# CHM_A_32_ver1_1.net
KiCad netlist of a schematic drawn in EasyEDA Pro
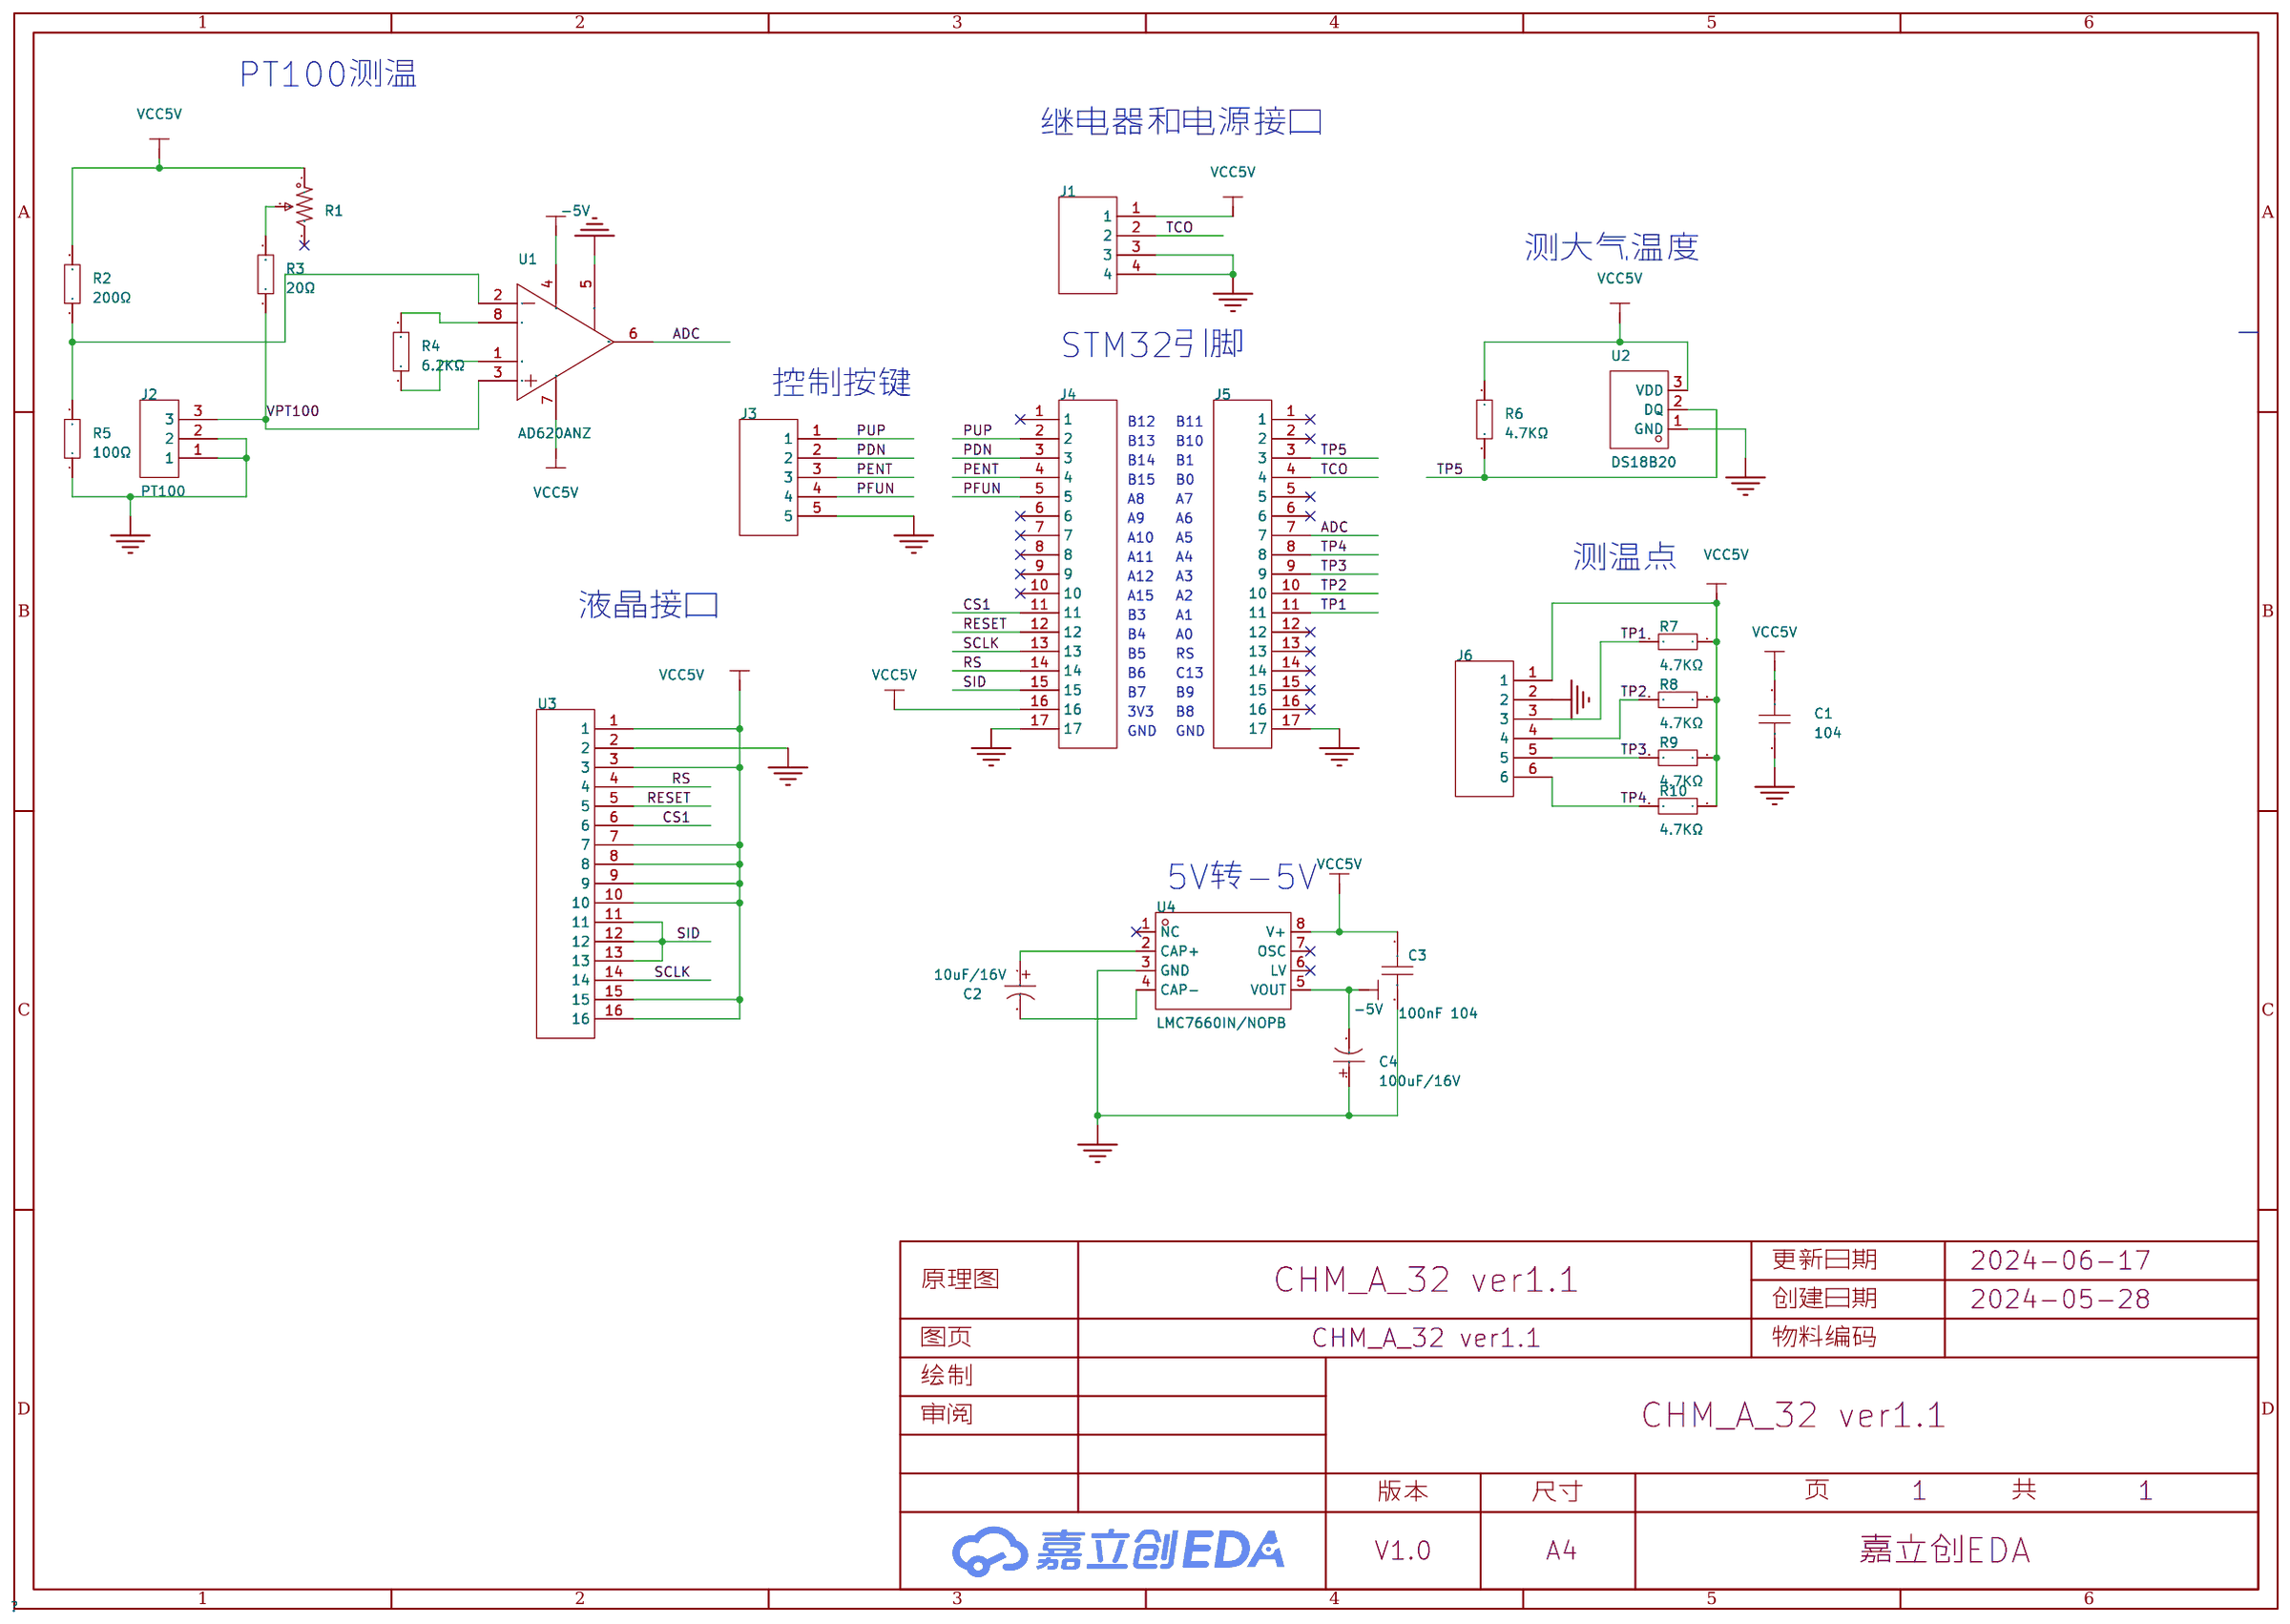
[diagram p0: schematic sheet]

(export (version "E")
  (design (tool "Eeschema 10.0.6"))
  (components
    (comp (ref "C1") (value "104") (libsource (lib "easyedapro") (part "插件电容")))
    (comp (ref "C2")
      (value "10uF/16V")
      (footprint "easyedapro:CAP-SMD_BD4.0-L4.3-W4.3-LS5.0-FD")
      (description "容值:10uF;精度:±20%;额定电压:16V;纹波电流:-;等效串联电阻:-;")
      (fields (field (name "Manufacturer Part") "RVT1C100M0405") (field (name "Manufacturer") "HONOR(荣誉)"))
      (libsource (lib "easyedapro") (part "RVT1C100M0405"))
    )
    (comp (ref "C3")
      (value "100nF 104")
      (footprint "easyedapro:C0402")
      (description "容值:100nF;精度:±10%;额定电压:50V;材质(温度系数):X7R;")
      (fields
        (field (name "Manufacturer Part") "CL05B104KB54PNC")
        (field (name "Manufacturer") "SAMSUNG(三星)")
      )
      (libsource (lib "easyedapro") (part "CL05B104KB54PNC"))
    )
    (comp (ref "C4")
      (value "100uF/16V")
      (footprint "easyedapro:CAP-SMD_BD6.3-L6.6-W6.6-LS7.2-FD")
      (description "容值:100uF;精度:±20%;额定电压:16V;纹波电流:-;等效串联电阻:-;")
      (fields (field (name "Manufacturer Part") "RVT1C101M0605") (field (name "Manufacturer") "HONOR(荣誉)"))
      (libsource (lib "easyedapro") (part "RVT1C101M0605"))
    )
    (comp (ref "J1") (value "~") (libsource (lib "easyedapro") (part "HDR-4P")))
    (comp (ref "J2") (value "PT100") (libsource (lib "easyedapro") (part "HDR-3P")))
    (comp (ref "J3") (value "~") (libsource (lib "easyedapro") (part "HDR-5P")))
    (comp (ref "J4") (value "~") (libsource (lib "easyedapro") (part "HDR-17P")))
    (comp (ref "J5") (value "~") (libsource (lib "easyedapro") (part "HDR-17P")))
    (comp (ref "J6") (value "~") (libsource (lib "easyedapro") (part "HDR-6P")))
    (comp (ref "R1")
      (value "？")
      (footprint "easyedapro:RES-ADJ-TH_3P-L10.0-W10.0-P2.50-L")
      (description "阻值:10kΩ;精度:±10%;")
      (fields (field (name "Manufacturer Part") "3296W-1-103") (field (name "Manufacturer") "BOCHEN(博晨)"))
      (libsource (lib "easyedapro") (part "3296W-1-103"))
    )
    (comp (ref "R2") (value "200Ω") (libsource (lib "easyedapro") (part "插件电阻")))
    (comp (ref "R3") (value "20Ω") (libsource (lib "easyedapro") (part "插件电阻")))
    (comp (ref "R4") (value "6.2KΩ") (libsource (lib "easyedapro") (part "插件电阻")))
    (comp (ref "R5") (value "100Ω") (libsource (lib "easyedapro") (part "插件电阻")))
    (comp (ref "R6") (value "4.7KΩ") (libsource (lib "easyedapro") (part "插件电阻")))
    (comp (ref "R7") (value "4.7KΩ") (libsource (lib "easyedapro") (part "插件电阻")))
    (comp (ref "R8") (value "4.7KΩ") (libsource (lib "easyedapro") (part "插件电阻")))
    (comp (ref "R9") (value "4.7KΩ") (libsource (lib "easyedapro") (part "插件电阻")))
    (comp (ref "R10") (value "4.7KΩ") (libsource (lib "easyedapro") (part "插件电阻")))
    (comp (ref "U1")
      (value "AD620ANZ")
      (footprint "easyedapro:DIP-8_L9.3-W6.4-P2.54-LS7.6-BL")
      (description "放大器数:单路;输入偏置电流(Ib):500pA;输入失调电压(Vos):30uV;增益带宽积(GBP):-;压摆率(SR):1.2V/us;带宽(-3db):1MHz;")
      (fields (field (name "Manufacturer") "ADI(亚德诺)"))
      (libsource (lib "easyedapro") (part "AD620ANZ"))
    )
    (comp (ref "U2")
      (value "DS18B20")
      (footprint "easyedapro:TO-92-3_L4.9-W3.7-P1.27-L")
      (description "温度范围:-55°C~+125°C;精度:±0.4°C;接口类型:-;")
      (fields (field (name "Manufacturer") "UMW(友台半导体)"))
      (libsource (lib "easyedapro") (part "DS18B20"))
    )
    (comp (ref "U3")
      (value "~")
      (footprint "easyedapro:CH2.54-16P")
      (libsource (lib "easyedapro") (part "HDR-16P"))
    )
    (comp (ref "U4")
      (value "LMC7660IN/NOPB")
      (footprint "easyedapro:PDIP-8_L9.6-W6.4-P2.54-LS7.6-BL")
      (description "功能类型:-;输出类型:固定;输入电压:1.5V~10V;输出电流(最大值):-;")
      (fields (field (name "Manufacturer") "TI(德州仪器)"))
      (libsource (lib "easyedapro") (part "LMC7660IN/NOPB"))
    )
  )
  (nets
    (net (code "1") (name "-5V") (class "Default")
      (node (ref "C4") (pin "2") (pinfunction "2_2") (pintype "input"))
      (node (ref "U1") (pin "4") (pinfunction "-VS_4") (pintype "unspecified"))
      (node (ref "U4") (pin "5") (pinfunction "VOUT_5") (pintype "unspecified"))
    )
    (net (code "2") (name "/ADC") (class "Default")
      (node (ref "J5") (pin "7") (pinfunction "7_7") (pintype "input"))
      (node (ref "U1") (pin "6") (pinfunction "OUTPUT_6") (pintype "output"))
    )
    (net (code "3") (name "/CS1") (class "Default")
      (node (ref "J4") (pin "11") (pinfunction "11_11") (pintype "input"))
      (node (ref "U3") (pin "6") (pinfunction "6_6") (pintype "input"))
    )
    (net (code "4") (name "/PDN") (class "Default")
      (node (ref "J3") (pin "2") (pinfunction "2_2") (pintype "input"))
      (node (ref "J4") (pin "3") (pinfunction "3_3") (pintype "input"))
    )
    (net (code "5") (name "/PENT") (class "Default")
      (node (ref "J3") (pin "3") (pinfunction "3_3") (pintype "input"))
      (node (ref "J4") (pin "4") (pinfunction "4_4") (pintype "input"))
    )
    (net (code "6") (name "/PFUN") (class "Default")
      (node (ref "J3") (pin "4") (pinfunction "4_4") (pintype "input"))
      (node (ref "J4") (pin "5") (pinfunction "5_5") (pintype "input"))
    )
    (net (code "7") (name "/PUP") (class "Default")
      (node (ref "J3") (pin "1") (pinfunction "1_1") (pintype "input"))
      (node (ref "J4") (pin "2") (pinfunction "2_2") (pintype "input"))
    )
    (net (code "8") (name "/RESET") (class "Default")
      (node (ref "J4") (pin "12") (pinfunction "12_12") (pintype "input"))
      (node (ref "U3") (pin "5") (pinfunction "5_5") (pintype "input"))
    )
    (net (code "9") (name "/RS") (class "Default")
      (node (ref "J4") (pin "14") (pinfunction "14_14") (pintype "input"))
      (node (ref "U3") (pin "4") (pinfunction "4_4") (pintype "input"))
    )
    (net (code "10") (name "/SCLK") (class "Default")
      (node (ref "J4") (pin "13") (pinfunction "13_13") (pintype "input"))
      (node (ref "U3") (pin "14") (pinfunction "14_14") (pintype "input"))
    )
    (net (code "11") (name "/SID") (class "Default")
      (node (ref "J4") (pin "15") (pinfunction "15_15") (pintype "input"))
      (node (ref "U3") (pin "11") (pinfunction "11_11") (pintype "input"))
      (node (ref "U3") (pin "12") (pinfunction "12_12") (pintype "input"))
      (node (ref "U3") (pin "13") (pinfunction "13_13") (pintype "input"))
    )
    (net (code "12") (name "/TCO") (class "Default")
      (node (ref "J1") (pin "2") (pinfunction "2_2") (pintype "input"))
      (node (ref "J5") (pin "4") (pinfunction "4_4") (pintype "input"))
    )
    (net (code "13") (name "/TP1") (class "Default")
      (node (ref "J5") (pin "11") (pinfunction "11_11") (pintype "input"))
      (node (ref "J6") (pin "3") (pinfunction "3_3") (pintype "input"))
      (node (ref "R7") (pin "2") (pinfunction "2_2") (pintype "input"))
    )
    (net (code "14") (name "/TP2") (class "Default")
      (node (ref "J5") (pin "10") (pinfunction "10_10") (pintype "input"))
      (node (ref "J6") (pin "4") (pinfunction "4_4") (pintype "input"))
      (node (ref "R8") (pin "2") (pinfunction "2_2") (pintype "input"))
    )
    (net (code "15") (name "/TP3") (class "Default")
      (node (ref "J5") (pin "9") (pinfunction "9_9") (pintype "input"))
      (node (ref "J6") (pin "5") (pinfunction "5_5") (pintype "input"))
      (node (ref "R9") (pin "2") (pinfunction "2_2") (pintype "input"))
    )
    (net (code "16") (name "/TP4") (class "Default")
      (node (ref "J5") (pin "8") (pinfunction "8_8") (pintype "input"))
      (node (ref "J6") (pin "6") (pinfunction "6_6") (pintype "input"))
      (node (ref "R10") (pin "2") (pinfunction "2_2") (pintype "input"))
    )
    (net (code "17") (name "/TP5") (class "Default")
      (node (ref "J5") (pin "3") (pinfunction "3_3") (pintype "input"))
      (node (ref "R6") (pin "2") (pinfunction "2_2") (pintype "input"))
      (node (ref "U2") (pin "2") (pinfunction "DQ_2") (pintype "unspecified"))
    )
    (net (code "18") (name "/VPT100") (class "Default")
      (node (ref "J2") (pin "3") (pinfunction "3_3") (pintype "input"))
      (node (ref "R3") (pin "1") (pinfunction "1_1") (pintype "input"))
      (node (ref "U1") (pin "3") (pinfunction "+IN_3") (pintype "input"))
    )
    (net (code "19") (name "GND") (class "Default")
      (node (ref "C1") (pin "1") (pinfunction "1_1") (pintype "unspecified"))
      (node (ref "C3") (pin "2") (pinfunction "2_2") (pintype "input"))
      (node (ref "C4") (pin "1") (pinfunction "1_1") (pintype "input"))
      (node (ref "J1") (pin "3") (pinfunction "3_3") (pintype "input"))
      (node (ref "J1") (pin "4") (pinfunction "4_4") (pintype "input"))
      (node (ref "J2") (pin "1") (pinfunction "1_1") (pintype "input"))
      (node (ref "J2") (pin "2") (pinfunction "2_2") (pintype "input"))
      (node (ref "J3") (pin "5") (pinfunction "5_5") (pintype "input"))
      (node (ref "J4") (pin "17") (pinfunction "17_17") (pintype "input"))
      (node (ref "J5") (pin "17") (pinfunction "17_17") (pintype "input"))
      (node (ref "J6") (pin "2") (pinfunction "2_2") (pintype "input"))
      (node (ref "R5") (pin "1") (pinfunction "1_1") (pintype "input"))
      (node (ref "U1") (pin "5") (pinfunction "REF_5") (pintype "input"))
      (node (ref "U2") (pin "1") (pinfunction "GND_1") (pintype "unspecified"))
      (node (ref "U3") (pin "2") (pinfunction "2_2") (pintype "input"))
      (node (ref "U4") (pin "3") (pinfunction "GND_3") (pintype "unspecified"))
    )
    (net (code "20") (name "Net-(R1-Pad2)") (class "Default")
      (node (ref "R1") (pin "2") (pinfunction "2_2") (pintype "input"))
      (node (ref "R3") (pin "2") (pinfunction "2_2") (pintype "input"))
    )
    (net (code "21") (name "Net-(R4-Pad1)") (class "Default")
      (node (ref "R4") (pin "1") (pinfunction "1_1") (pintype "input"))
      (node (ref "U1") (pin "1") (pinfunction "RG_1") (pintype "unspecified"))
    )
    (net (code "22") (name "Net-(R4-Pad2)") (class "Default")
      (node (ref "R4") (pin "2") (pinfunction "2_2") (pintype "input"))
      (node (ref "U1") (pin "8") (pinfunction "RG_8") (pintype "unspecified"))
    )
    (net (code "23") (name "Net-(U1--IN)") (class "Default")
      (node (ref "R2") (pin "1") (pinfunction "1_1") (pintype "input"))
      (node (ref "R5") (pin "2") (pinfunction "2_2") (pintype "input"))
      (node (ref "U1") (pin "2") (pinfunction "-IN_2") (pintype "input"))
    )
    (net (code "24") (name "Net-(U4-CAP+)") (class "Default")
      (node (ref "C2") (pin "1") (pinfunction "1_1") (pintype "input"))
      (node (ref "U4") (pin "2") (pinfunction "CAP+_2") (pintype "unspecified"))
    )
    (net (code "25") (name "Net-(U4-CAP-)") (class "Default")
      (node (ref "C2") (pin "2") (pinfunction "2_2") (pintype "input"))
      (node (ref "U4") (pin "4") (pinfunction "CAP-_4") (pintype "unspecified"))
    )
    (net (code "26") (name "VCC5V") (class "Default")
      (node (ref "C1") (pin "2") (pinfunction "2_2") (pintype "unspecified"))
      (node (ref "C3") (pin "1") (pinfunction "1_1") (pintype "input"))
      (node (ref "J1") (pin "1") (pinfunction "1_1") (pintype "input"))
      (node (ref "J4") (pin "16") (pinfunction "16_16") (pintype "input"))
      (node (ref "J6") (pin "1") (pinfunction "1_1") (pintype "input"))
      (node (ref "R1") (pin "1") (pinfunction "1_1") (pintype "input"))
      (node (ref "R10") (pin "1") (pinfunction "1_1") (pintype "input"))
      (node (ref "R2") (pin "2") (pinfunction "2_2") (pintype "input"))
      (node (ref "R6") (pin "1") (pinfunction "1_1") (pintype "input"))
      (node (ref "R7") (pin "1") (pinfunction "1_1") (pintype "input"))
      (node (ref "R8") (pin "1") (pinfunction "1_1") (pintype "input"))
      (node (ref "R9") (pin "1") (pinfunction "1_1") (pintype "input"))
      (node (ref "U1") (pin "7") (pinfunction "+VS_7") (pintype "unspecified"))
      (node (ref "U2") (pin "3") (pinfunction "VDD_3") (pintype "unspecified"))
      (node (ref "U3") (pin "1") (pinfunction "1_1") (pintype "input"))
      (node (ref "U3") (pin "10") (pinfunction "10_10") (pintype "input"))
      (node (ref "U3") (pin "15") (pinfunction "15_15") (pintype "input"))
      (node (ref "U3") (pin "16") (pinfunction "16_16") (pintype "input"))
      (node (ref "U3") (pin "3") (pinfunction "3_3") (pintype "input"))
      (node (ref "U3") (pin "7") (pinfunction "7_7") (pintype "input"))
      (node (ref "U3") (pin "8") (pinfunction "8_8") (pintype "input"))
      (node (ref "U3") (pin "9") (pinfunction "9_9") (pintype "input"))
      (node (ref "U4") (pin "8") (pinfunction "V+_8") (pintype "unspecified"))
    )
    (net (code "27") (name "unconnected-(J4-Pad1)") (class "Default")
      (node (ref "J4") (pin "1") (pinfunction "1_1") (pintype "input+no_connect"))
    )
    (net (code "28") (name "unconnected-(J4-Pad6)") (class "Default")
      (node (ref "J4") (pin "6") (pinfunction "6_6") (pintype "input+no_connect"))
    )
    (net (code "29") (name "unconnected-(J4-Pad7)") (class "Default")
      (node (ref "J4") (pin "7") (pinfunction "7_7") (pintype "input+no_connect"))
    )
    (net (code "30") (name "unconnected-(J4-Pad8)") (class "Default")
      (node (ref "J4") (pin "8") (pinfunction "8_8") (pintype "input+no_connect"))
    )
    (net (code "31") (name "unconnected-(J4-Pad9)") (class "Default")
      (node (ref "J4") (pin "9") (pinfunction "9_9") (pintype "input+no_connect"))
    )
    (net (code "32") (name "unconnected-(J4-Pad10)") (class "Default")
      (node (ref "J4") (pin "10") (pinfunction "10_10") (pintype "input+no_connect"))
    )
    (net (code "33") (name "unconnected-(J5-Pad1)") (class "Default")
      (node (ref "J5") (pin "1") (pinfunction "1_1") (pintype "input+no_connect"))
    )
    (net (code "34") (name "unconnected-(J5-Pad2)") (class "Default")
      (node (ref "J5") (pin "2") (pinfunction "2_2") (pintype "input+no_connect"))
    )
    (net (code "35") (name "unconnected-(J5-Pad5)") (class "Default")
      (node (ref "J5") (pin "5") (pinfunction "5_5") (pintype "input+no_connect"))
    )
    (net (code "36") (name "unconnected-(J5-Pad6)") (class "Default")
      (node (ref "J5") (pin "6") (pinfunction "6_6") (pintype "input+no_connect"))
    )
    (net (code "37") (name "unconnected-(J5-Pad12)") (class "Default")
      (node (ref "J5") (pin "12") (pinfunction "12_12") (pintype "input+no_connect"))
    )
    (net (code "38") (name "unconnected-(J5-Pad13)") (class "Default")
      (node (ref "J5") (pin "13") (pinfunction "13_13") (pintype "input+no_connect"))
    )
    (net (code "39") (name "unconnected-(J5-Pad14)") (class "Default")
      (node (ref "J5") (pin "14") (pinfunction "14_14") (pintype "input+no_connect"))
    )
    (net (code "40") (name "unconnected-(J5-Pad15)") (class "Default")
      (node (ref "J5") (pin "15") (pinfunction "15_15") (pintype "input+no_connect"))
    )
    (net (code "41") (name "unconnected-(J5-Pad16)") (class "Default")
      (node (ref "J5") (pin "16") (pinfunction "16_16") (pintype "input+no_connect"))
    )
    (net (code "42") (name "unconnected-(R1-Pad3)") (class "Default")
      (node (ref "R1") (pin "3") (pinfunction "3_3") (pintype "input+no_connect"))
    )
    (net (code "43") (name "unconnected-(U4-LV-Pad6)") (class "Default")
      (node (ref "U4") (pin "6") (pinfunction "LV_6") (pintype "unspecified+no_connect"))
    )
    (net (code "44") (name "unconnected-(U4-NC-Pad1)") (class "Default")
      (node (ref "U4") (pin "1") (pinfunction "NC_1") (pintype "unspecified+no_connect"))
    )
    (net (code "45") (name "unconnected-(U4-OSC-Pad7)") (class "Default")
      (node (ref "U4") (pin "7") (pinfunction "OSC_7") (pintype "unspecified+no_connect"))
    )
  )
)
